# power-carrier.net
KiCad netlist of a schematic drawn in EAGLE
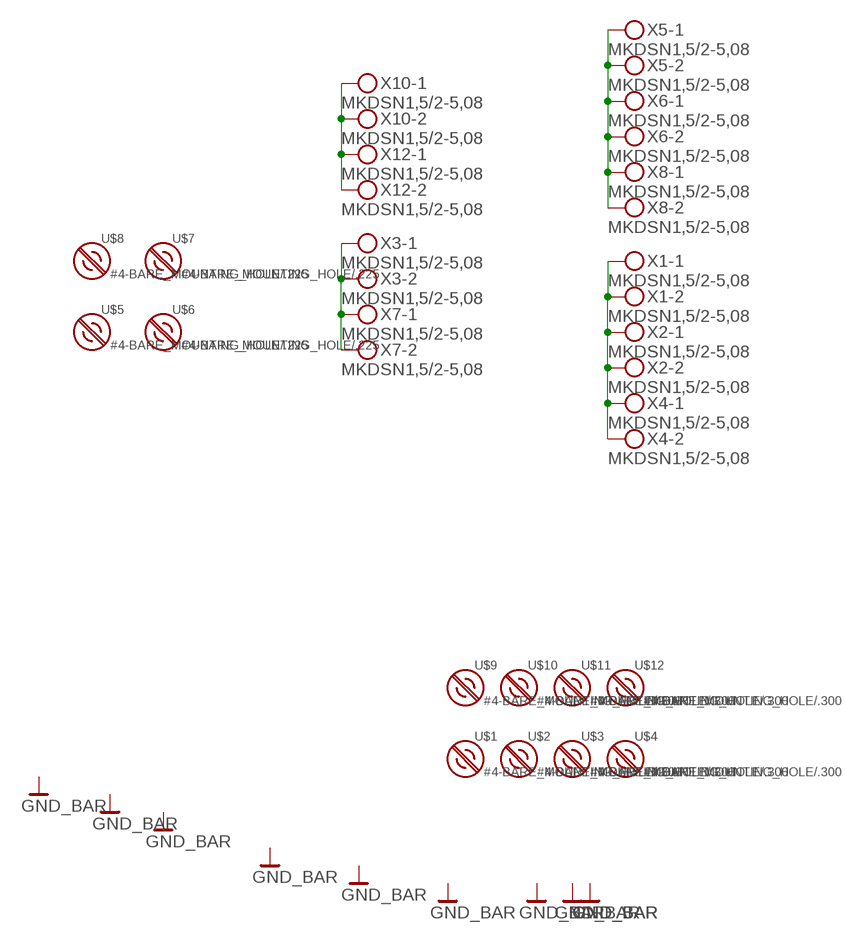
[diagram p0: schematic, sheet 1]

(export (version "E")
  (design (tool "Eeschema 10.0.6"))
  (components
    (comp (ref "U$1")
      (value "#4-BARE_MOUNTING_HOLE/.300")
      (footprint "eagle-import:#4_.300-BARE+STD_NUT_OR_STAR_WASHER")
      (libsource (lib "eagle-import") (part "#4-BARE_MOUNTING_HOLE/.300"))
    )
    (comp (ref "U$2")
      (value "#4-BARE_MOUNTING_HOLE/.300")
      (footprint "eagle-import:#4_.300-BARE+STD_NUT_OR_STAR_WASHER")
      (libsource (lib "eagle-import") (part "#4-BARE_MOUNTING_HOLE/.300"))
    )
    (comp (ref "U$3")
      (value "#4-BARE_MOUNTING_HOLE/.300")
      (footprint "eagle-import:#4_.300-BARE+STD_NUT_OR_STAR_WASHER")
      (libsource (lib "eagle-import") (part "#4-BARE_MOUNTING_HOLE/.300"))
    )
    (comp (ref "U$4")
      (value "#4-BARE_MOUNTING_HOLE/.300")
      (footprint "eagle-import:#4_.300-BARE+STD_NUT_OR_STAR_WASHER")
      (libsource (lib "eagle-import") (part "#4-BARE_MOUNTING_HOLE/.300"))
    )
    (comp (ref "U$5")
      (value "#4-BARE_MOUNTING_HOLE/.225")
      (footprint "eagle-import:#4_.225-BARE+HEAD_OR_SMALL_NUT")
      (libsource (lib "eagle-import") (part "#4-BARE_MOUNTING_HOLE/.225"))
    )
    (comp (ref "U$6")
      (value "#4-BARE_MOUNTING_HOLE/.225")
      (footprint "eagle-import:#4_.225-BARE+HEAD_OR_SMALL_NUT")
      (libsource (lib "eagle-import") (part "#4-BARE_MOUNTING_HOLE/.225"))
    )
    (comp (ref "U$7")
      (value "#4-BARE_MOUNTING_HOLE/.225")
      (footprint "eagle-import:#4_.225-BARE+HEAD_OR_SMALL_NUT")
      (libsource (lib "eagle-import") (part "#4-BARE_MOUNTING_HOLE/.225"))
    )
    (comp (ref "U$8")
      (value "#4-BARE_MOUNTING_HOLE/.225")
      (footprint "eagle-import:#4_.225-BARE+HEAD_OR_SMALL_NUT")
      (libsource (lib "eagle-import") (part "#4-BARE_MOUNTING_HOLE/.225"))
    )
    (comp (ref "U$9")
      (value "#4-BARE_MOUNTING_HOLE/.300")
      (footprint "eagle-import:#4_.300-BARE+STD_NUT_OR_STAR_WASHER")
      (libsource (lib "eagle-import") (part "#4-BARE_MOUNTING_HOLE/.300"))
    )
    (comp (ref "U$10")
      (value "#4-BARE_MOUNTING_HOLE/.300")
      (footprint "eagle-import:#4_.300-BARE+STD_NUT_OR_STAR_WASHER")
      (libsource (lib "eagle-import") (part "#4-BARE_MOUNTING_HOLE/.300"))
    )
    (comp (ref "U$11")
      (value "#4-BARE_MOUNTING_HOLE/.300")
      (footprint "eagle-import:#4_.300-BARE+STD_NUT_OR_STAR_WASHER")
      (libsource (lib "eagle-import") (part "#4-BARE_MOUNTING_HOLE/.300"))
    )
    (comp (ref "U$12")
      (value "#4-BARE_MOUNTING_HOLE/.300")
      (footprint "eagle-import:#4_.300-BARE+STD_NUT_OR_STAR_WASHER")
      (libsource (lib "eagle-import") (part "#4-BARE_MOUNTING_HOLE/.300"))
    )
    (comp (ref "X1")
      (value "MKDSN1,5/2-5,08")
      (footprint "eagle-import:MKDSN1,5_2-5,08")
      (fields (field (name "MPN") "MKDSN 1,5/2-5.08"))
      (libsource (lib "eagle-import") (part "MKDSN1,5/2-5,08"))
    )
    (comp (ref "X2")
      (value "MKDSN1,5/2-5,08")
      (footprint "eagle-import:MKDSN1,5_2-5,08")
      (fields (field (name "MPN") "MKDSN 1,5/2-5.08"))
      (libsource (lib "eagle-import") (part "MKDSN1,5/2-5,08"))
    )
    (comp (ref "X3")
      (value "MKDSN1,5/2-5,08")
      (footprint "eagle-import:MKDSN1,5_2-5,08")
      (fields (field (name "MPN") "MKDSN 1,5/2-5.08"))
      (libsource (lib "eagle-import") (part "MKDSN1,5/2-5,08"))
    )
    (comp (ref "X4")
      (value "MKDSN1,5/2-5,08")
      (footprint "eagle-import:MKDSN1,5_2-5,08")
      (fields
        (field (name "MPN") "MKDSN 1,5/2-5.08")
        (field (name "MPN_1") "MKDSN 1,5/2-5.08")
        (field (name "OC_FARNELL") "1792903")
        (field (name "OC_NEWARK") "30M2397")
      )
      (libsource (lib "eagle-import") (part "MKDSN1,5/2-5,08"))
    )
    (comp (ref "X5")
      (value "MKDSN1,5/2-5,08")
      (footprint "eagle-import:MKDSN1,5_2-5,08")
      (fields (field (name "MPN") "MKDSN 1,5/2-5.08"))
      (libsource (lib "eagle-import") (part "MKDSN1,5/2-5,08"))
    )
    (comp (ref "X6")
      (value "MKDSN1,5/2-5,08")
      (footprint "eagle-import:MKDSN1,5_2-5,08")
      (fields (field (name "MPN") "MKDSN 1,5/2-5.08"))
      (libsource (lib "eagle-import") (part "MKDSN1,5/2-5,08"))
    )
    (comp (ref "X7")
      (value "MKDSN1,5/2-5,08")
      (footprint "eagle-import:MKDSN1,5_2-5,08")
      (fields (field (name "MPN") "MKDSN 1,5/2-5.08"))
      (libsource (lib "eagle-import") (part "MKDSN1,5/2-5,08"))
    )
    (comp (ref "X8")
      (value "MKDSN1,5/2-5,08")
      (footprint "eagle-import:MKDSN1,5_2-5,08")
      (fields
        (field (name "MPN") "MKDSN 1,5/2-5.08")
        (field (name "MPN_1") "MKDSN 1,5/2-5.08")
        (field (name "OC_FARNELL") "1792903")
        (field (name "OC_NEWARK") "30M2397")
      )
      (libsource (lib "eagle-import") (part "MKDSN1,5/2-5,08"))
    )
    (comp (ref "X10")
      (value "MKDSN1,5/2-5,08")
      (footprint "eagle-import:MKDSN1,5_2-5,08")
      (fields (field (name "MPN") "MKDSN 1,5/2-5.08"))
      (libsource (lib "eagle-import") (part "MKDSN1,5/2-5,08"))
    )
    (comp (ref "X12")
      (value "MKDSN1,5/2-5,08")
      (footprint "eagle-import:MKDSN1,5_2-5,08")
      (fields
        (field (name "MPN") "MKDSN 1,5/2-5.08")
        (field (name "MPN_1") "MKDSN 1,5/2-5.08")
        (field (name "OC_FARNELL") "1792903")
        (field (name "OC_NEWARK") "30M2397")
      )
      (libsource (lib "eagle-import") (part "MKDSN1,5/2-5,08"))
    )
  )
  (nets
    (net (code "1") (name "/GND") (class "Default")
      (node (ref "X1") (pin "1") (pinfunction "KL_1") (pintype "passive"))
      (node (ref "X1") (pin "2") (pinfunction "KL_2") (pintype "passive"))
      (node (ref "X10") (pin "1") (pinfunction "KL_1") (pintype "passive"))
      (node (ref "X10") (pin "2") (pinfunction "KL_2") (pintype "passive"))
      (node (ref "X12") (pin "1") (pinfunction "KL_1") (pintype "passive"))
      (node (ref "X12") (pin "2") (pinfunction "KL_2") (pintype "passive"))
      (node (ref "X2") (pin "1") (pinfunction "KL_1") (pintype "passive"))
      (node (ref "X2") (pin "2") (pinfunction "KL_2") (pintype "passive"))
      (node (ref "X4") (pin "1") (pinfunction "KL_1") (pintype "passive"))
      (node (ref "X4") (pin "2") (pinfunction "KL_2") (pintype "passive"))
    )
    (net (code "2") (name "/VBAT") (class "Default")
      (node (ref "X3") (pin "1") (pinfunction "KL_1") (pintype "passive"))
      (node (ref "X3") (pin "2") (pinfunction "KL_2") (pintype "passive"))
      (node (ref "X5") (pin "1") (pinfunction "KL_1") (pintype "passive"))
      (node (ref "X5") (pin "2") (pinfunction "KL_2") (pintype "passive"))
      (node (ref "X6") (pin "1") (pinfunction "KL_1") (pintype "passive"))
      (node (ref "X6") (pin "2") (pinfunction "KL_2") (pintype "passive"))
      (node (ref "X7") (pin "1") (pinfunction "KL_1") (pintype "passive"))
      (node (ref "X7") (pin "2") (pinfunction "KL_2") (pintype "passive"))
      (node (ref "X8") (pin "1") (pinfunction "KL_1") (pintype "passive"))
      (node (ref "X8") (pin "2") (pinfunction "KL_2") (pintype "passive"))
    )
  )
)
